# WorkingPlaftorm.net
KiCad netlist of a schematic drawn in EAGLE
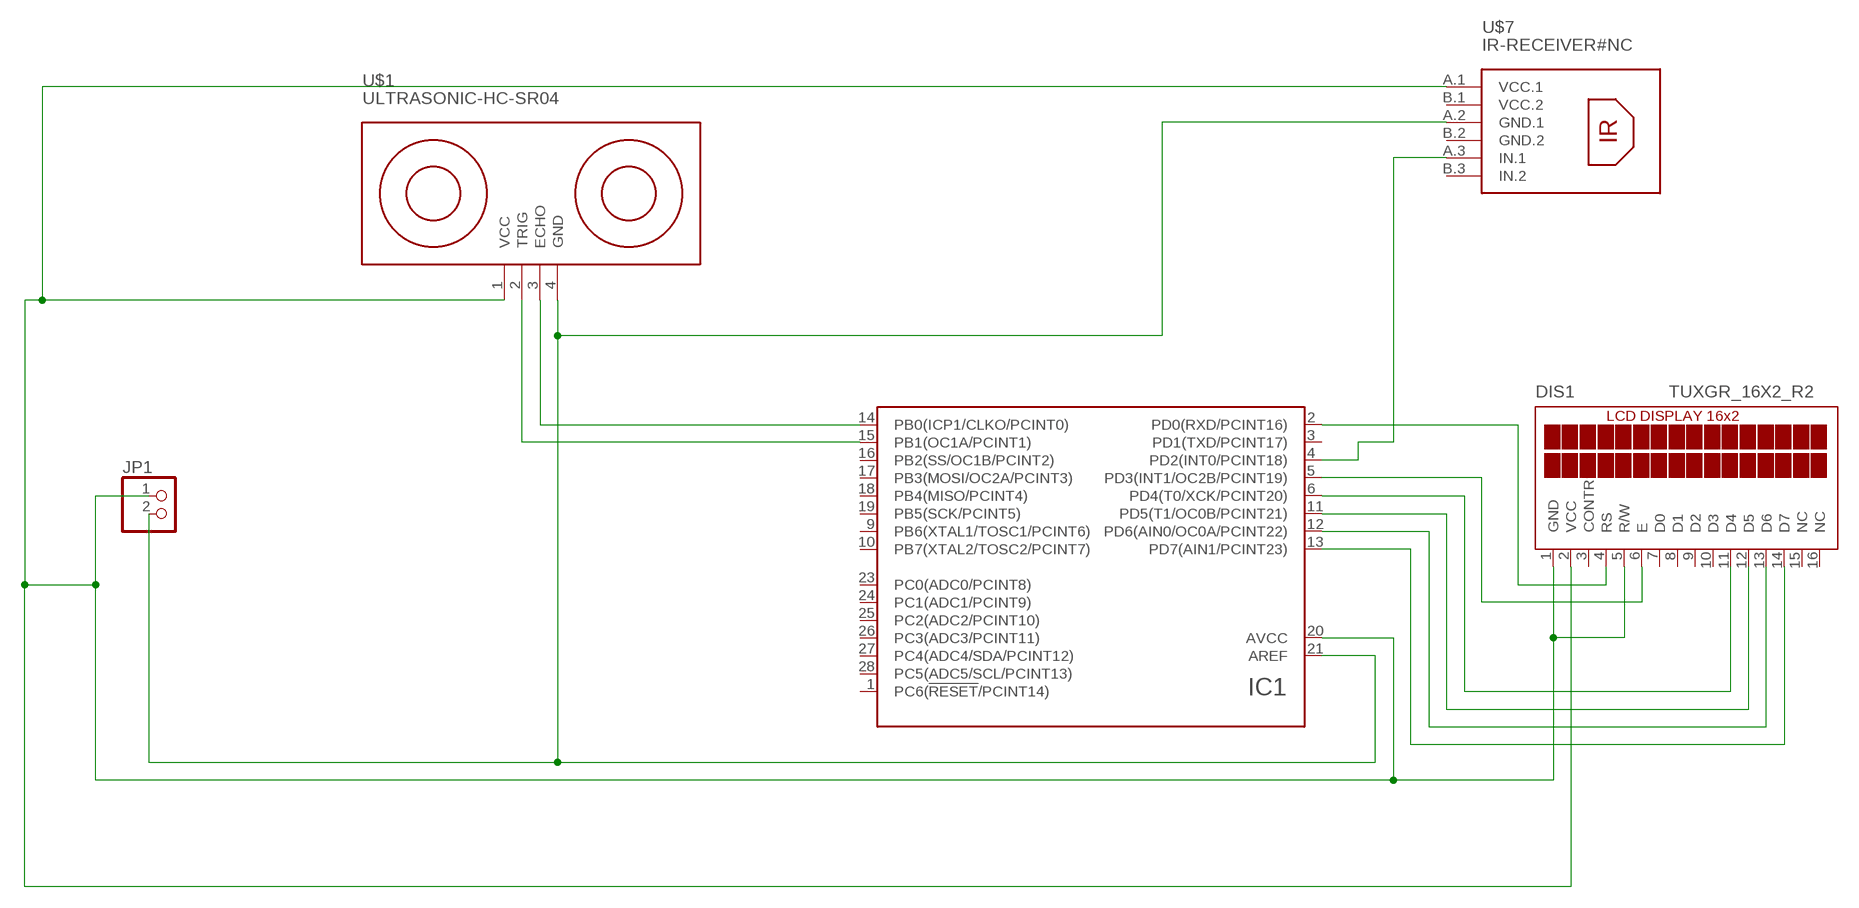
[diagram p0: schematic, sheet 1]

(export (version "E")
  (design (tool "Eeschema 10.0.6"))
  (components
    (comp (ref "DIS1")
      (value "TUXGR_16X2_R2")
      (footprint "eagle-import:TUXGR_16X2_R2")
      (libsource (lib "eagle-import") (part "TUXGR_16X2_R2"))
    )
    (comp (ref "IC1")
      (value "ATMEGA48/88/168/328-PU(DIP28)PU")
      (footprint "eagle-import:DIL28")
      (libsource (lib "eagle-import") (part "ATMEGA48/88/168/328-PU(DIP28)PU"))
    )
    (comp (ref "JP1")
      (value "PINHD-1X2")
      (footprint "eagle-import:1X02")
      (libsource (lib "eagle-import") (part "PINHD-1X2"))
    )
    (comp (ref "U$1")
      (value "ULTRASONIC-HC-SR04")
      (footprint "eagle-import:ULTRASONIC-HC-SR04")
      (libsource (lib "eagle-import") (part "ULTRASONIC-HC-SR04"))
    )
    (comp (ref "U$7")
      (value "IR-RECEIVER#NC")
      (footprint "eagle-import:IR-RECEIVER#NC")
      (libsource (lib "eagle-import") (part "IR-RECEIVER#NC"))
    )
  )
  (nets
    (net (code "1") (name "Net-(DIS1-D4)") (class "Default")
      (node (ref "DIS1") (pin "11") (pinfunction "D4_11") (pintype "input"))
      (node (ref "IC1") (pin "6") (pinfunction "PD4(T0/XCK/PCINT20)_6") (pintype "bidirectional"))
    )
    (net (code "2") (name "Net-(DIS1-D5)") (class "Default")
      (node (ref "DIS1") (pin "12") (pinfunction "D5_12") (pintype "input"))
      (node (ref "IC1") (pin "11") (pinfunction "PD5(T1/OC0B/PCINT21)_11") (pintype "bidirectional"))
    )
    (net (code "3") (name "Net-(DIS1-D6)") (class "Default")
      (node (ref "DIS1") (pin "13") (pinfunction "D6_13") (pintype "input"))
      (node (ref "IC1") (pin "12") (pinfunction "PD6(AIN0/OC0A/PCINT22)_12") (pintype "bidirectional"))
    )
    (net (code "4") (name "Net-(DIS1-D7)") (class "Default")
      (node (ref "DIS1") (pin "14") (pinfunction "D7_14") (pintype "input"))
      (node (ref "IC1") (pin "13") (pinfunction "PD7(AIN1/PCINT23)_13") (pintype "bidirectional"))
    )
    (net (code "5") (name "Net-(DIS1-E)") (class "Default")
      (node (ref "DIS1") (pin "6") (pinfunction "E_6") (pintype "input"))
      (node (ref "IC1") (pin "5") (pinfunction "PD3(INT1/OC2B/PCINT19)_5") (pintype "bidirectional"))
    )
    (net (code "6") (name "Net-(DIS1-GND)") (class "Default")
      (node (ref "DIS1") (pin "1") (pinfunction "GND_1") (pintype "power_in"))
      (node (ref "DIS1") (pin "2") (pinfunction "VCC_2") (pintype "power_in"))
      (node (ref "DIS1") (pin "5") (pinfunction "R/W_5") (pintype "input"))
      (node (ref "IC1") (pin "20") (pinfunction "AVCC_20") (pintype "power_in"))
      (node (ref "JP1") (pin "1") (pinfunction "1_1") (pintype "passive"))
      (node (ref "U$1") (pin "1") (pinfunction "VCC_1") (pintype "power_in"))
      (node (ref "U$7") (pin "A.1") (pinfunction "VCC.1_A.1") (pintype "bidirectional"))
    )
    (net (code "7") (name "Net-(DIS1-RS)") (class "Default")
      (node (ref "DIS1") (pin "4") (pinfunction "RS_4") (pintype "input"))
      (node (ref "IC1") (pin "2") (pinfunction "PD0(RXD/PCINT16)_2") (pintype "bidirectional"))
    )
    (net (code "8") (name "Net-(IC1A-AREF)") (class "Default")
      (node (ref "IC1") (pin "21") (pinfunction "AREF_21") (pintype "passive"))
      (node (ref "JP1") (pin "2") (pinfunction "2_2") (pintype "passive"))
      (node (ref "U$1") (pin "4") (pinfunction "GND_4") (pintype "power_in"))
      (node (ref "U$7") (pin "A.2") (pinfunction "GND.1_A.2") (pintype "bidirectional"))
    )
    (net (code "9") (name "Net-(IC1A-PB0(ICP1{slash}CLKO{slash}PCINT0))") (class "Default")
      (node (ref "IC1") (pin "14") (pinfunction "PB0(ICP1/CLKO/PCINT0)_14") (pintype "bidirectional"))
      (node (ref "U$1") (pin "3") (pinfunction "ECHO_3") (pintype "output"))
    )
    (net (code "10") (name "Net-(IC1A-PB1(OC1A{slash}PCINT1))") (class "Default")
      (node (ref "IC1") (pin "15") (pinfunction "PB1(OC1A/PCINT1)_15") (pintype "bidirectional"))
      (node (ref "U$1") (pin "2") (pinfunction "TRIG_2") (pintype "input"))
    )
    (net (code "11") (name "Net-(IC1A-PD2(INT0{slash}PCINT18))") (class "Default")
      (node (ref "IC1") (pin "4") (pinfunction "PD2(INT0/PCINT18)_4") (pintype "bidirectional"))
      (node (ref "U$7") (pin "A.3") (pinfunction "IN.1_A.3") (pintype "bidirectional"))
    )
    (net (code "12") (name "unconnected-(DIS1-CONTR-Pad3)") (class "Default")
      (node (ref "DIS1") (pin "3") (pinfunction "CONTR_3") (pintype "input"))
    )
    (net (code "13") (name "unconnected-(DIS1-D0-Pad7)") (class "Default")
      (node (ref "DIS1") (pin "7") (pinfunction "D0_7") (pintype "input"))
    )
    (net (code "14") (name "unconnected-(DIS1-D1-Pad8)") (class "Default")
      (node (ref "DIS1") (pin "8") (pinfunction "D1_8") (pintype "input"))
    )
    (net (code "15") (name "unconnected-(DIS1-D2-Pad9)") (class "Default")
      (node (ref "DIS1") (pin "9") (pinfunction "D2_9") (pintype "input"))
    )
    (net (code "16") (name "unconnected-(DIS1-D3-Pad10)") (class "Default")
      (node (ref "DIS1") (pin "10") (pinfunction "D3_10") (pintype "input"))
    )
    (net (code "17") (name "unconnected-(DIS1-NC-Pad15)") (class "Default")
      (node (ref "DIS1") (pin "15") (pinfunction "NC_15") (pintype "no_connect"))
    )
    (net (code "18") (name "unconnected-(DIS1-NC-Pad16)") (class "Default")
      (node (ref "DIS1") (pin "16") (pinfunction "NC_16") (pintype "no_connect"))
    )
    (net (code "19") (name "unconnected-(IC1A-PB2(SS{slash}OC1B{slash}PCINT2)-Pad16)") (class "Default")
      (node (ref "IC1") (pin "16") (pinfunction "PB2(SS/OC1B/PCINT2)_16") (pintype "bidirectional"))
    )
    (net (code "20") (name "unconnected-(IC1A-PB3(MOSI{slash}OC2A{slash}PCINT3)-Pad17)") (class "Default")
      (node (ref "IC1") (pin "17") (pinfunction "PB3(MOSI/OC2A/PCINT3)_17") (pintype "bidirectional"))
    )
    (net (code "21") (name "unconnected-(IC1A-PB4(MISO{slash}PCINT4)-Pad18)") (class "Default")
      (node (ref "IC1") (pin "18") (pinfunction "PB4(MISO/PCINT4)_18") (pintype "bidirectional"))
    )
    (net (code "22") (name "unconnected-(IC1A-PB5(SCK{slash}PCINT5)-Pad19)") (class "Default")
      (node (ref "IC1") (pin "19") (pinfunction "PB5(SCK/PCINT5)_19") (pintype "bidirectional"))
    )
    (net (code "23") (name "unconnected-(IC1A-PB6(XTAL1{slash}TOSC1{slash}PCINT6)-Pad9)") (class "Default")
      (node (ref "IC1") (pin "9") (pinfunction "PB6(XTAL1/TOSC1/PCINT6)_9") (pintype "bidirectional"))
    )
    (net (code "24") (name "unconnected-(IC1A-PB7(XTAL2{slash}TOSC2{slash}PCINT7)-Pad10)") (class "Default")
      (node (ref "IC1") (pin "10") (pinfunction "PB7(XTAL2/TOSC2/PCINT7)_10") (pintype "bidirectional"))
    )
    (net (code "25") (name "unconnected-(IC1A-PC0(ADC0{slash}PCINT8)-Pad23)") (class "Default")
      (node (ref "IC1") (pin "23") (pinfunction "PC0(ADC0/PCINT8)_23") (pintype "bidirectional"))
    )
    (net (code "26") (name "unconnected-(IC1A-PC1(ADC1{slash}PCINT9)-Pad24)") (class "Default")
      (node (ref "IC1") (pin "24") (pinfunction "PC1(ADC1/PCINT9)_24") (pintype "bidirectional"))
    )
    (net (code "27") (name "unconnected-(IC1A-PC2(ADC2{slash}PCINT10)-Pad25)") (class "Default")
      (node (ref "IC1") (pin "25") (pinfunction "PC2(ADC2/PCINT10)_25") (pintype "bidirectional"))
    )
    (net (code "28") (name "unconnected-(IC1A-PC3(ADC3{slash}PCINT11)-Pad26)") (class "Default")
      (node (ref "IC1") (pin "26") (pinfunction "PC3(ADC3/PCINT11)_26") (pintype "bidirectional"))
    )
    (net (code "29") (name "unconnected-(IC1A-PC4(ADC4{slash}SDA{slash}PCINT12)-Pad27)") (class "Default")
      (node (ref "IC1") (pin "27") (pinfunction "PC4(ADC4/SDA/PCINT12)_27") (pintype "bidirectional"))
    )
    (net (code "30") (name "unconnected-(IC1A-PC5(ADC5{slash}SCL{slash}PCINT13)-Pad28)") (class "Default")
      (node (ref "IC1") (pin "28") (pinfunction "PC5(ADC5/SCL/PCINT13)_28") (pintype "bidirectional"))
    )
    (net (code "31") (name "unconnected-(IC1A-PC6(~{RESET}{slash}PCINT14)-Pad1)") (class "Default")
      (node (ref "IC1") (pin "1") (pinfunction "PC6(~{RESET}/PCINT14)_1") (pintype "bidirectional"))
    )
    (net (code "32") (name "unconnected-(IC1A-PD1(TXD{slash}PCINT17)-Pad3)") (class "Default")
      (node (ref "IC1") (pin "3") (pinfunction "PD1(TXD/PCINT17)_3") (pintype "bidirectional"))
    )
    (net (code "33") (name "unconnected-(U$7-GND.2-PadB.2)") (class "Default")
      (node (ref "U$7") (pin "B.2") (pinfunction "GND.2_B.2") (pintype "bidirectional"))
    )
    (net (code "34") (name "unconnected-(U$7-IN.2-PadB.3)") (class "Default")
      (node (ref "U$7") (pin "B.3") (pinfunction "IN.2_B.3") (pintype "bidirectional"))
    )
    (net (code "35") (name "unconnected-(U$7-VCC.2-PadB.1)") (class "Default")
      (node (ref "U$7") (pin "B.1") (pinfunction "VCC.2_B.1") (pintype "bidirectional"))
    )
  )
)
